# Murata_D1U54P_Power_Supply_Adapter_rev2.net
KiCad netlist of a schematic drawn in EAGLE
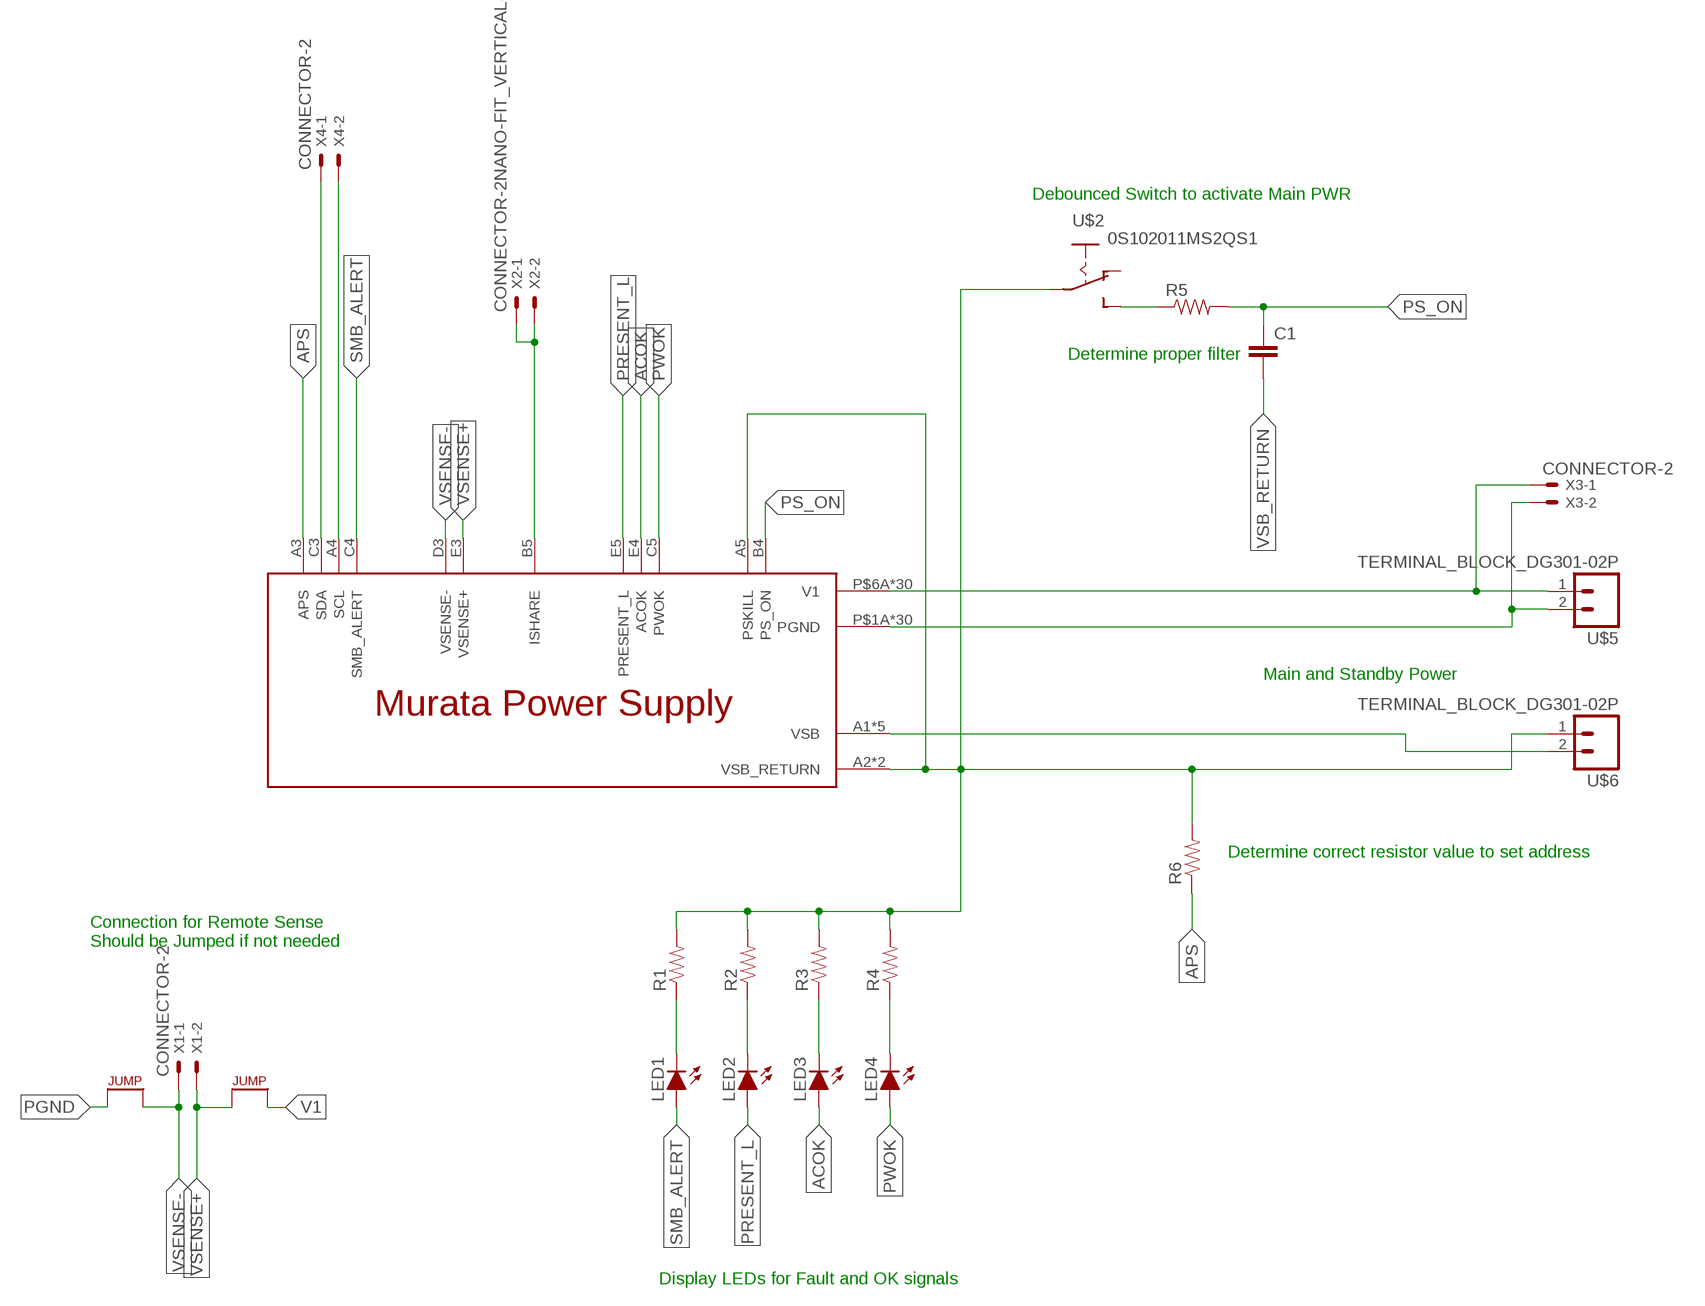
[diagram p0: schematic, sheet 1]

(export (version "E")
  (design (tool "Eeschema 10.0.6"))
  (components
    (comp (ref "C1")
      (value "CAP0805")
      (footprint "eagle-import:0805")
      (libsource (lib "eagle-import") (part "CAP0805"))
    )
    (comp (ref "LED1")
      (value "LED-0805")
      (footprint "eagle-import:LED-805")
      (libsource (lib "eagle-import") (part "LED-0805"))
    )
    (comp (ref "LED2")
      (value "LED-0805")
      (footprint "eagle-import:LED-805")
      (libsource (lib "eagle-import") (part "LED-0805"))
    )
    (comp (ref "LED3")
      (value "LED-0805")
      (footprint "eagle-import:LED-805")
      (libsource (lib "eagle-import") (part "LED-0805"))
    )
    (comp (ref "LED4")
      (value "LED-0805")
      (footprint "eagle-import:LED-805")
      (libsource (lib "eagle-import") (part "LED-0805"))
    )
    (comp (ref "R1")
      (value "RESISTOR0805-RES")
      (footprint "eagle-import:0805")
      (libsource (lib "eagle-import") (part "RESISTOR0805-RES"))
    )
    (comp (ref "R2")
      (value "RESISTOR0805-RES")
      (footprint "eagle-import:0805")
      (libsource (lib "eagle-import") (part "RESISTOR0805-RES"))
    )
    (comp (ref "R3")
      (value "RESISTOR0805-RES")
      (footprint "eagle-import:0805")
      (libsource (lib "eagle-import") (part "RESISTOR0805-RES"))
    )
    (comp (ref "R4")
      (value "RESISTOR0805-RES")
      (footprint "eagle-import:0805")
      (libsource (lib "eagle-import") (part "RESISTOR0805-RES"))
    )
    (comp (ref "R5")
      (value "RESISTOR0805-RES")
      (footprint "eagle-import:0805")
      (libsource (lib "eagle-import") (part "RESISTOR0805-RES"))
    )
    (comp (ref "R6")
      (value "RESISTOR0805-RES")
      (footprint "eagle-import:0805")
      (libsource (lib "eagle-import") (part "RESISTOR0805-RES"))
    )
    (comp (ref "U$1")
      (value "MURATA_POWER_SUPPLY")
      (footprint "eagle-import:MURATA_POWER_SUPPLY_CONNECTOR")
      (libsource (lib "eagle-import") (part "MURATA_POWER_SUPPLY"))
    )
    (comp (ref "U$2")
      (value "0S102011MS2QS1")
      (footprint "eagle-import:0S102011MS2QS1")
      (libsource (lib "eagle-import") (part "0S102011MS2QS1"))
    )
    (comp (ref "U$3")
      (value "JUMPER.1")
      (footprint "eagle-import:1X02")
      (libsource (lib "eagle-import") (part "JUMPER.1"))
    )
    (comp (ref "U$4")
      (value "JUMPER.1")
      (footprint "eagle-import:1X02")
      (libsource (lib "eagle-import") (part "JUMPER.1"))
    )
    (comp (ref "U$5")
      (value "TERMINAL_BLOCK_DG301-02P")
      (footprint "eagle-import:DG301-02P")
      (libsource (lib "eagle-import") (part "TERMINAL_BLOCK_DG301-02P"))
    )
    (comp (ref "U$6")
      (value "TERMINAL_BLOCK_DG301-02P")
      (footprint "eagle-import:DG301-02P")
      (libsource (lib "eagle-import") (part "TERMINAL_BLOCK_DG301-02P"))
    )
    (comp (ref "X1")
      (value "CONNECTOR-2")
      (footprint "eagle-import:MINIFIT_5566-2")
      (libsource (lib "eagle-import") (part "CONNECTOR-2"))
    )
    (comp (ref "X2")
      (value "CONNECTOR-2NANO-FIT_VERTICAL-2")
      (footprint "eagle-import:NANO-FIT_VERTICAL-2")
      (libsource (lib "eagle-import") (part "CONNECTOR-2NANO-FIT_VERTICAL-2"))
    )
    (comp (ref "X3")
      (value "CONNECTOR-2")
      (footprint "eagle-import:MINIFIT_5566-2")
      (libsource (lib "eagle-import") (part "CONNECTOR-2"))
    )
    (comp (ref "X4")
      (value "CONNECTOR-2")
      (footprint "eagle-import:MINIFIT_5566-2")
      (libsource (lib "eagle-import") (part "CONNECTOR-2"))
    )
  )
  (nets
    (net (code "1") (name "ACOK") (class "Default")
      (node (ref "LED3") (pin "A") (pinfunction "A_A") (pintype "passive"))
      (node (ref "U$1") (pin "E4") (pinfunction "ACOK_E4") (pintype "bidirectional"))
    )
    (net (code "2") (name "APS") (class "Default")
      (node (ref "R6") (pin "1") (pinfunction "1_1") (pintype "passive"))
      (node (ref "U$1") (pin "A3") (pinfunction "APS_A3") (pintype "bidirectional"))
    )
    (net (code "3") (name "Net-(LED1-PadC)") (class "Default")
      (node (ref "LED1") (pin "C") (pinfunction "C_C") (pintype "passive"))
      (node (ref "R1") (pin "1") (pinfunction "1_1") (pintype "passive"))
    )
    (net (code "4") (name "Net-(LED2-PadC)") (class "Default")
      (node (ref "LED2") (pin "C") (pinfunction "C_C") (pintype "passive"))
      (node (ref "R2") (pin "1") (pinfunction "1_1") (pintype "passive"))
    )
    (net (code "5") (name "Net-(LED3-PadC)") (class "Default")
      (node (ref "LED3") (pin "C") (pinfunction "C_C") (pintype "passive"))
      (node (ref "R3") (pin "1") (pinfunction "1_1") (pintype "passive"))
    )
    (net (code "6") (name "Net-(LED4-PadC)") (class "Default")
      (node (ref "LED4") (pin "C") (pinfunction "C_C") (pintype "passive"))
      (node (ref "R4") (pin "1") (pinfunction "1_1") (pintype "passive"))
    )
    (net (code "7") (name "Net-(U$1-ISHARE)") (class "Default")
      (node (ref "U$1") (pin "B5") (pinfunction "ISHARE_B5") (pintype "bidirectional"))
      (node (ref "X2") (pin "P$1") (pinfunction "S_P$1") (pintype "passive"))
      (node (ref "X2") (pin "P$2") (pinfunction "S_P$2") (pintype "passive"))
    )
    (net (code "8") (name "Net-(U$1-SCL)") (class "Default")
      (node (ref "U$1") (pin "A4") (pinfunction "SCL_A4") (pintype "bidirectional"))
      (node (ref "X4") (pin "2") (pinfunction "S_2") (pintype "passive"))
    )
    (net (code "9") (name "Net-(U$1-SDA)") (class "Default")
      (node (ref "U$1") (pin "C3") (pinfunction "SDA_C3") (pintype "bidirectional"))
      (node (ref "X4") (pin "1") (pinfunction "S_1") (pintype "passive"))
    )
    (net (code "10") (name "Net-(U$1-VSB-PadA1)") (class "Default")
      (node (ref "U$1") (pin "A1") (pinfunction "VSB_A1") (pintype "bidirectional"))
      (node (ref "U$1") (pin "B1") (pinfunction "VSB_B1") (pintype "bidirectional"))
      (node (ref "U$1") (pin "C1") (pinfunction "VSB_C1") (pintype "bidirectional"))
      (node (ref "U$1") (pin "D1") (pinfunction "VSB_D1") (pintype "bidirectional"))
      (node (ref "U$1") (pin "E1") (pinfunction "VSB_E1") (pintype "bidirectional"))
      (node (ref "U$6") (pin "2") (pinfunction "2_2") (pintype "passive"))
    )
    (net (code "11") (name "Net-(U$2-S)") (class "Default")
      (node (ref "R5") (pin "1") (pinfunction "1_1") (pintype "passive"))
      (node (ref "U$2") (pin "P$3") (pinfunction "S_P$3") (pintype "passive"))
    )
    (net (code "12") (name "PGND") (class "Default")
      (node (ref "U$1") (pin "P$1A") (pinfunction "PGND_P$1A") (pintype "bidirectional"))
      (node (ref "U$1") (pin "P$1B") (pinfunction "PGND_P$1B") (pintype "bidirectional"))
      (node (ref "U$1") (pin "P$1C") (pinfunction "PGND_P$1C") (pintype "bidirectional"))
      (node (ref "U$1") (pin "P$1D") (pinfunction "PGND_P$1D") (pintype "bidirectional"))
      (node (ref "U$1") (pin "P$1E") (pinfunction "PGND_P$1E") (pintype "bidirectional"))
      (node (ref "U$1") (pin "P$1F") (pinfunction "PGND_P$1F") (pintype "bidirectional"))
      (node (ref "U$1") (pin "P$2A") (pinfunction "PGND_P$2A") (pintype "bidirectional"))
      (node (ref "U$1") (pin "P$2B") (pinfunction "PGND_P$2B") (pintype "bidirectional"))
      (node (ref "U$1") (pin "P$2C") (pinfunction "PGND_P$2C") (pintype "bidirectional"))
      (node (ref "U$1") (pin "P$2D") (pinfunction "PGND_P$2D") (pintype "bidirectional"))
      (node (ref "U$1") (pin "P$2E") (pinfunction "PGND_P$2E") (pintype "bidirectional"))
      (node (ref "U$1") (pin "P$2F") (pinfunction "PGND_P$2F") (pintype "bidirectional"))
      (node (ref "U$1") (pin "P$3A") (pinfunction "PGND_P$3A") (pintype "bidirectional"))
      (node (ref "U$1") (pin "P$3B") (pinfunction "PGND_P$3B") (pintype "bidirectional"))
      (node (ref "U$1") (pin "P$3C") (pinfunction "PGND_P$3C") (pintype "bidirectional"))
      (node (ref "U$1") (pin "P$3D") (pinfunction "PGND_P$3D") (pintype "bidirectional"))
      (node (ref "U$1") (pin "P$3E") (pinfunction "PGND_P$3E") (pintype "bidirectional"))
      (node (ref "U$1") (pin "P$3F") (pinfunction "PGND_P$3F") (pintype "bidirectional"))
      (node (ref "U$1") (pin "P$4A") (pinfunction "PGND_P$4A") (pintype "bidirectional"))
      (node (ref "U$1") (pin "P$4B") (pinfunction "PGND_P$4B") (pintype "bidirectional"))
      (node (ref "U$1") (pin "P$4C") (pinfunction "PGND_P$4C") (pintype "bidirectional"))
      (node (ref "U$1") (pin "P$4D") (pinfunction "PGND_P$4D") (pintype "bidirectional"))
      (node (ref "U$1") (pin "P$4E") (pinfunction "PGND_P$4E") (pintype "bidirectional"))
      (node (ref "U$1") (pin "P$4F") (pinfunction "PGND_P$4F") (pintype "bidirectional"))
      (node (ref "U$1") (pin "P$5A") (pinfunction "PGND_P$5A") (pintype "bidirectional"))
      (node (ref "U$1") (pin "P$5B") (pinfunction "PGND_P$5B") (pintype "bidirectional"))
      (node (ref "U$1") (pin "P$5C") (pinfunction "PGND_P$5C") (pintype "bidirectional"))
      (node (ref "U$1") (pin "P$5D") (pinfunction "PGND_P$5D") (pintype "bidirectional"))
      (node (ref "U$1") (pin "P$5E") (pinfunction "PGND_P$5E") (pintype "bidirectional"))
      (node (ref "U$1") (pin "P$5F") (pinfunction "PGND_P$5F") (pintype "bidirectional"))
      (node (ref "U$4") (pin "1") (pinfunction "P$1_1") (pintype "bidirectional"))
      (node (ref "U$5") (pin "2") (pinfunction "2_2") (pintype "passive"))
      (node (ref "X3") (pin "2") (pinfunction "S_2") (pintype "passive"))
    )
    (net (code "13") (name "PRESENT_L") (class "Default")
      (node (ref "LED2") (pin "A") (pinfunction "A_A") (pintype "passive"))
      (node (ref "U$1") (pin "E5") (pinfunction "PRESENT_L_E5") (pintype "bidirectional"))
    )
    (net (code "14") (name "PS_ON") (class "Default")
      (node (ref "C1") (pin "1") (pinfunction "1_1") (pintype "passive"))
      (node (ref "R5") (pin "2") (pinfunction "2_2") (pintype "passive"))
      (node (ref "U$1") (pin "B4") (pinfunction "PS_ON_B4") (pintype "bidirectional"))
    )
    (net (code "15") (name "PWOK") (class "Default")
      (node (ref "LED4") (pin "A") (pinfunction "A_A") (pintype "passive"))
      (node (ref "U$1") (pin "C5") (pinfunction "PWOK_C5") (pintype "bidirectional"))
    )
    (net (code "16") (name "SMB_ALERT") (class "Default")
      (node (ref "LED1") (pin "A") (pinfunction "A_A") (pintype "passive"))
      (node (ref "U$1") (pin "C4") (pinfunction "SMB_ALERT_C4") (pintype "bidirectional"))
    )
    (net (code "17") (name "V1") (class "Default")
      (node (ref "U$1") (pin "P$10A") (pinfunction "V1_P$10A") (pintype "bidirectional"))
      (node (ref "U$1") (pin "P$10B") (pinfunction "V1_P$10B") (pintype "bidirectional"))
      (node (ref "U$1") (pin "P$10C") (pinfunction "V1_P$10C") (pintype "bidirectional"))
      (node (ref "U$1") (pin "P$10D") (pinfunction "V1_P$10D") (pintype "bidirectional"))
      (node (ref "U$1") (pin "P$10E") (pinfunction "V1_P$10E") (pintype "bidirectional"))
      (node (ref "U$1") (pin "P$10F") (pinfunction "V1_P$10F") (pintype "bidirectional"))
      (node (ref "U$1") (pin "P$6A") (pinfunction "V1_P$6A") (pintype "bidirectional"))
      (node (ref "U$1") (pin "P$6B") (pinfunction "V1_P$6B") (pintype "bidirectional"))
      (node (ref "U$1") (pin "P$6C") (pinfunction "V1_P$6C") (pintype "bidirectional"))
      (node (ref "U$1") (pin "P$6D") (pinfunction "V1_P$6D") (pintype "bidirectional"))
      (node (ref "U$1") (pin "P$6E") (pinfunction "V1_P$6E") (pintype "bidirectional"))
      (node (ref "U$1") (pin "P$6F") (pinfunction "V1_P$6F") (pintype "bidirectional"))
      (node (ref "U$1") (pin "P$7A") (pinfunction "V1_P$7A") (pintype "bidirectional"))
      (node (ref "U$1") (pin "P$7B") (pinfunction "V1_P$7B") (pintype "bidirectional"))
      (node (ref "U$1") (pin "P$7C") (pinfunction "V1_P$7C") (pintype "bidirectional"))
      (node (ref "U$1") (pin "P$7D") (pinfunction "V1_P$7D") (pintype "bidirectional"))
      (node (ref "U$1") (pin "P$7E") (pinfunction "V1_P$7E") (pintype "bidirectional"))
      (node (ref "U$1") (pin "P$7F") (pinfunction "V1_P$7F") (pintype "bidirectional"))
      (node (ref "U$1") (pin "P$8A") (pinfunction "V1_P$8A") (pintype "bidirectional"))
      (node (ref "U$1") (pin "P$8B") (pinfunction "V1_P$8B") (pintype "bidirectional"))
      (node (ref "U$1") (pin "P$8C") (pinfunction "V1_P$8C") (pintype "bidirectional"))
      (node (ref "U$1") (pin "P$8D") (pinfunction "V1_P$8D") (pintype "bidirectional"))
      (node (ref "U$1") (pin "P$8E") (pinfunction "V1_P$8E") (pintype "bidirectional"))
      (node (ref "U$1") (pin "P$8F") (pinfunction "V1_P$8F") (pintype "bidirectional"))
      (node (ref "U$1") (pin "P$9A") (pinfunction "V1_P$9A") (pintype "bidirectional"))
      (node (ref "U$1") (pin "P$9B") (pinfunction "V1_P$9B") (pintype "bidirectional"))
      (node (ref "U$1") (pin "P$9C") (pinfunction "V1_P$9C") (pintype "bidirectional"))
      (node (ref "U$1") (pin "P$9D") (pinfunction "V1_P$9D") (pintype "bidirectional"))
      (node (ref "U$1") (pin "P$9E") (pinfunction "V1_P$9E") (pintype "bidirectional"))
      (node (ref "U$1") (pin "P$9F") (pinfunction "V1_P$9F") (pintype "bidirectional"))
      (node (ref "U$3") (pin "2") (pinfunction "P$2_2") (pintype "bidirectional"))
      (node (ref "U$5") (pin "1") (pinfunction "1_1") (pintype "passive"))
      (node (ref "X3") (pin "1") (pinfunction "S_1") (pintype "passive"))
    )
    (net (code "18") (name "VSB_RETURN") (class "Default")
      (node (ref "C1") (pin "2") (pinfunction "2_2") (pintype "passive"))
      (node (ref "R1") (pin "2") (pinfunction "2_2") (pintype "passive"))
      (node (ref "R2") (pin "2") (pinfunction "2_2") (pintype "passive"))
      (node (ref "R3") (pin "2") (pinfunction "2_2") (pintype "passive"))
      (node (ref "R4") (pin "2") (pinfunction "2_2") (pintype "passive"))
      (node (ref "R6") (pin "2") (pinfunction "2_2") (pintype "passive"))
      (node (ref "U$1") (pin "A2") (pinfunction "VSB_RETURN_A2") (pintype "bidirectional"))
      (node (ref "U$1") (pin "A5") (pinfunction "PSKILL_A5") (pintype "bidirectional"))
      (node (ref "U$1") (pin "B2") (pinfunction "VSB_RETURN_B2") (pintype "bidirectional"))
      (node (ref "U$2") (pin "P$2") (pinfunction "P_P$2") (pintype "passive"))
      (node (ref "U$6") (pin "1") (pinfunction "1_1") (pintype "passive"))
    )
    (net (code "19") (name "VSENSE+") (class "Default")
      (node (ref "U$1") (pin "E3") (pinfunction "VSENSE+_E3") (pintype "bidirectional"))
      (node (ref "U$3") (pin "1") (pinfunction "P$1_1") (pintype "bidirectional"))
      (node (ref "X1") (pin "2") (pinfunction "S_2") (pintype "passive"))
    )
    (net (code "20") (name "VSENSE-") (class "Default")
      (node (ref "U$1") (pin "D3") (pinfunction "VSENSE-_D3") (pintype "bidirectional"))
      (node (ref "U$4") (pin "2") (pinfunction "P$2_2") (pintype "bidirectional"))
      (node (ref "X1") (pin "1") (pinfunction "S_1") (pintype "passive"))
    )
    (net (code "21") (name "unconnected-(U$2-O-PadP$1)") (class "Default")
      (node (ref "U$2") (pin "P$1") (pinfunction "O_P$1") (pintype "passive"))
    )
  )
)
